# Netscale48HD_Sensorbar.net
KiCad netlist of a schematic drawn in Altium Designer
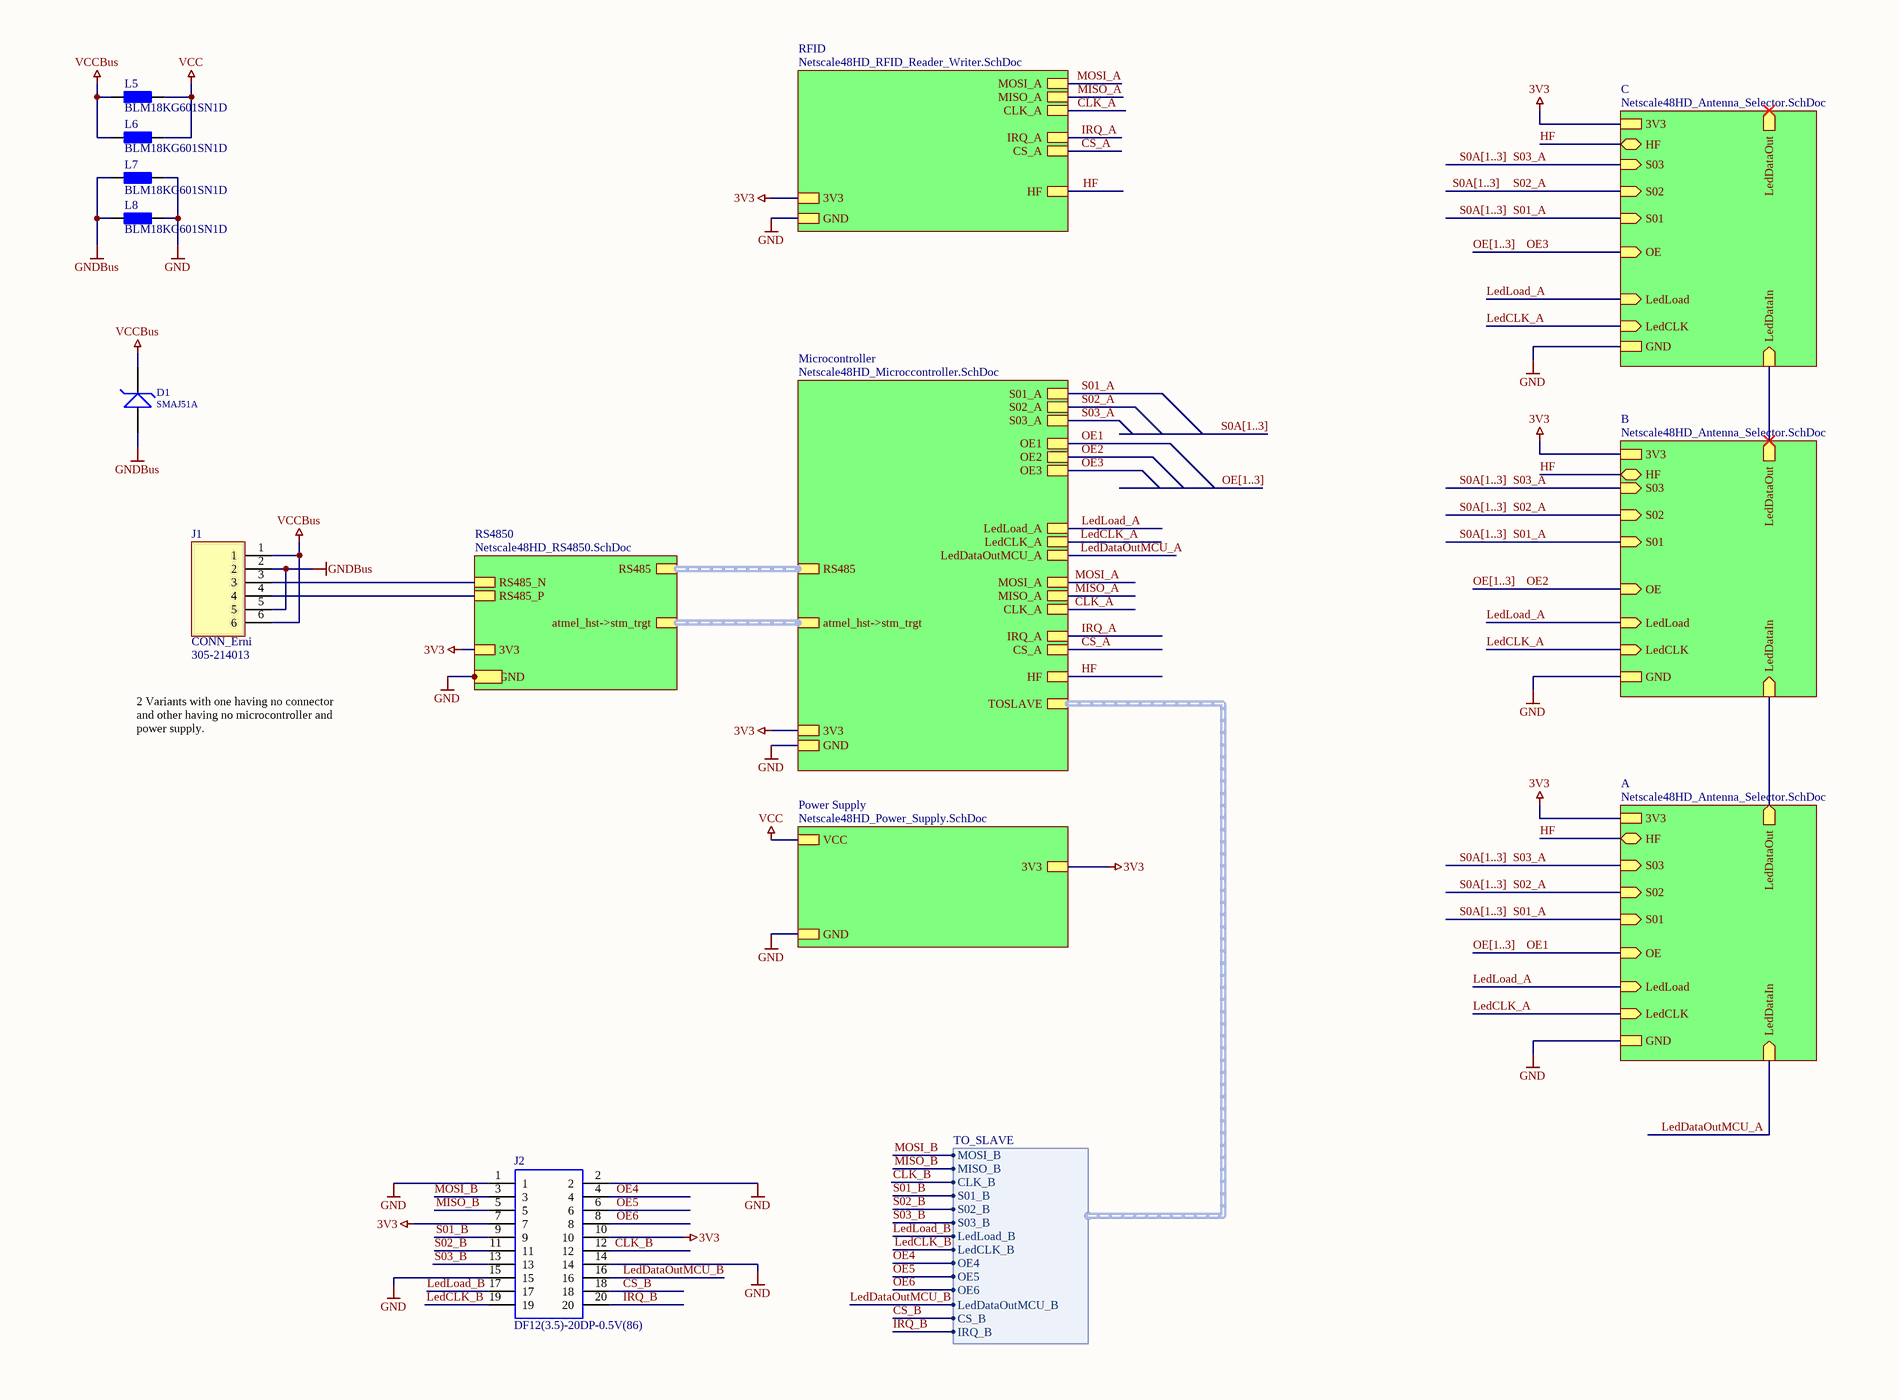
[diagram p0: Netscale48HD_Sensorbar.SchDoc, top]

(export (version "E")
  (design (tool "Eeschema 10.0.6"))
  (components
    (comp (ref "D1")
      (value "SMAJ51A")
      (footprint "Bourns_DO-214AC (SMA) small_2_R")
      (description "ESD Suppressors / TVS Diodes 51volts 5uA 4.9 Amps Uni-Dir")
      (fields (field (name "MANUFACTURER") "Bourns"))
      (libsource (lib "RDM_ALT_SCH") (part "Diode_SMAJ51A"))
    )
    (comp (ref "J1")
      (value "CONN_Erni")
      (footprint "ERNI_214013 Randmontage_6_R")
      (description "Headers & Wire Housings 6P 1.27MM SNGL ROW R/A MALE BLK")
      (fields (field (name "MANUFACTURER") "ERNI") (field (name "SUPPLIER PART NUMBER 1") "305-214013"))
      (libsource (lib "RDM_ALT_SCH") (part "CONN_Erni_6_214013"))
    )
    (comp (ref "J2")
      (value "DF12(3.5)-20DP-0.5V(86)")
      (footprint "DF12(4.0)-20DP")
      (fields
        (field (name "RS PART NUMBER") "6082064P")
        (field (name "MOUSER PART NUMBER") "798-DF123520DP0.5V86")
      )
      (libsource (lib "RDM_ALT_SCH") (part "DF12(3.5)-20DP-0.5V(86)"))
    )
    (comp (ref "L5")
      (value "BLM18KG601SN1D")
      (footprint "CAP-0603[1608] - RFL")
      (description "Chip Ferrite Bead")
      (fields (field (name "MANUFACTURER") "Murata"))
      (libsource (lib "RDM_Altium_Library") (part "Ferrite Beads"))
    )
    (comp (ref "L6")
      (value "BLM18KG601SN1D")
      (footprint "CAP-0603[1608] - RFL")
      (description "Chip Ferrite Bead")
      (fields (field (name "MANUFACTURER") "Murata"))
      (libsource (lib "RDM_Altium_Library") (part "Ferrite Beads"))
    )
    (comp (ref "L7")
      (value "BLM18KG601SN1D")
      (footprint "CAP-0603[1608] - RFL")
      (description "Chip Ferrite Bead")
      (fields (field (name "MANUFACTURER") "Murata"))
      (libsource (lib "RDM_Altium_Library") (part "Ferrite Beads"))
    )
    (comp (ref "L8")
      (value "BLM18KG601SN1D")
      (footprint "CAP-0603[1608] - RFL")
      (description "Chip Ferrite Bead")
      (fields (field (name "MANUFACTURER") "Murata"))
      (libsource (lib "RDM_Altium_Library") (part "Ferrite Beads"))
    )
  )
  (nets
    (net (code "6") (name "/CLK_B") (class "Default")
      (node (ref "J2") (pin "12") (pinfunction "12_12") (pintype "passive"))
    )
    (net (code "8") (name "/CS_B") (class "Default")
      (node (ref "J2") (pin "18") (pinfunction "18_18") (pintype "passive"))
    )
    (net (code "11") (name "/IRQ_B") (class "Default")
      (node (ref "J2") (pin "20") (pinfunction "20_20") (pintype "passive"))
    )
    (net (code "13") (name "/LedCLK_B") (class "Default")
      (node (ref "J2") (pin "19") (pinfunction "19_19") (pintype "passive"))
    )
    (net (code "16") (name "/LedDataOutMCU_B") (class "Default")
      (node (ref "J2") (pin "16") (pinfunction "16_16") (pintype "passive"))
    )
    (net (code "20") (name "/LedLoad_B") (class "Default")
      (node (ref "J2") (pin "17") (pinfunction "17_17") (pintype "passive"))
    )
    (net (code "22") (name "/MISO_B") (class "Default")
      (node (ref "J2") (pin "5") (pinfunction "5_5") (pintype "passive"))
    )
    (net (code "24") (name "/MOSI_B") (class "Default")
      (node (ref "J2") (pin "3") (pinfunction "3_3") (pintype "passive"))
    )
    (net (code "28") (name "/OE4") (class "Default")
      (node (ref "J2") (pin "4") (pinfunction "4_4") (pintype "passive"))
    )
    (net (code "29") (name "/OE5") (class "Default")
      (node (ref "J2") (pin "6") (pinfunction "6_6") (pintype "passive"))
    )
    (net (code "30") (name "/OE6") (class "Default")
      (node (ref "J2") (pin "8") (pinfunction "8_8") (pintype "passive"))
    )
    (net (code "32") (name "/RS485_N") (class "Default")
      (node (ref "J1") (pin "3") (pinfunction "3_3") (pintype "passive"))
    )
    (net (code "33") (name "/RS485_P") (class "Default")
      (node (ref "J1") (pin "4") (pinfunction "4_4") (pintype "passive"))
    )
    (net (code "37") (name "/S01_B") (class "Default")
      (node (ref "J2") (pin "9") (pinfunction "9_9") (pintype "passive"))
    )
    (net (code "39") (name "/S02_B") (class "Default")
      (node (ref "J2") (pin "11") (pinfunction "11_11") (pintype "passive"))
    )
    (net (code "41") (name "/S03_B") (class "Default")
      (node (ref "J2") (pin "13") (pinfunction "13_13") (pintype "passive"))
    )
    (net (code "44") (name "3V3") (class "Default")
      (node (ref "J2") (pin "10") (pinfunction "10_10") (pintype "passive"))
      (node (ref "J2") (pin "7") (pinfunction "7_7") (pintype "passive"))
    )
    (net (code "45") (name "GND") (class "Default")
      (node (ref "J2") (pin "1") (pinfunction "1_1") (pintype "passive"))
      (node (ref "J2") (pin "14") (pinfunction "14_14") (pintype "passive"))
      (node (ref "J2") (pin "15") (pinfunction "15_15") (pintype "passive"))
      (node (ref "J2") (pin "2") (pinfunction "2_2") (pintype "passive"))
      (node (ref "L7") (pin "2") (pinfunction "2_2") (pintype "passive"))
      (node (ref "L8") (pin "2") (pinfunction "2_2") (pintype "passive"))
    )
    (net (code "46") (name "GNDBus") (class "Default")
      (node (ref "D1") (pin "2") (pinfunction "A_2") (pintype "passive"))
      (node (ref "J1") (pin "2") (pinfunction "2_2") (pintype "passive"))
      (node (ref "J1") (pin "5") (pinfunction "5_5") (pintype "passive"))
      (node (ref "L7") (pin "1") (pinfunction "1_1") (pintype "passive"))
      (node (ref "L8") (pin "1") (pinfunction "1_1") (pintype "passive"))
    )
    (net (code "47") (name "VCC") (class "Default")
      (node (ref "L5") (pin "2") (pinfunction "2_2") (pintype "passive"))
      (node (ref "L6") (pin "2") (pinfunction "2_2") (pintype "passive"))
    )
    (net (code "48") (name "VCCBus") (class "Default")
      (node (ref "D1") (pin "1") (pinfunction "K_1") (pintype "passive"))
      (node (ref "J1") (pin "1") (pinfunction "1_1") (pintype "passive"))
      (node (ref "J1") (pin "6") (pinfunction "6_6") (pintype "passive"))
      (node (ref "L5") (pin "1") (pinfunction "1_1") (pintype "passive"))
      (node (ref "L6") (pin "1") (pinfunction "1_1") (pintype "passive"))
    )
  )
)
